# DaughterBoardInterface.net
KiCad netlist of a schematic drawn in Altium Designer
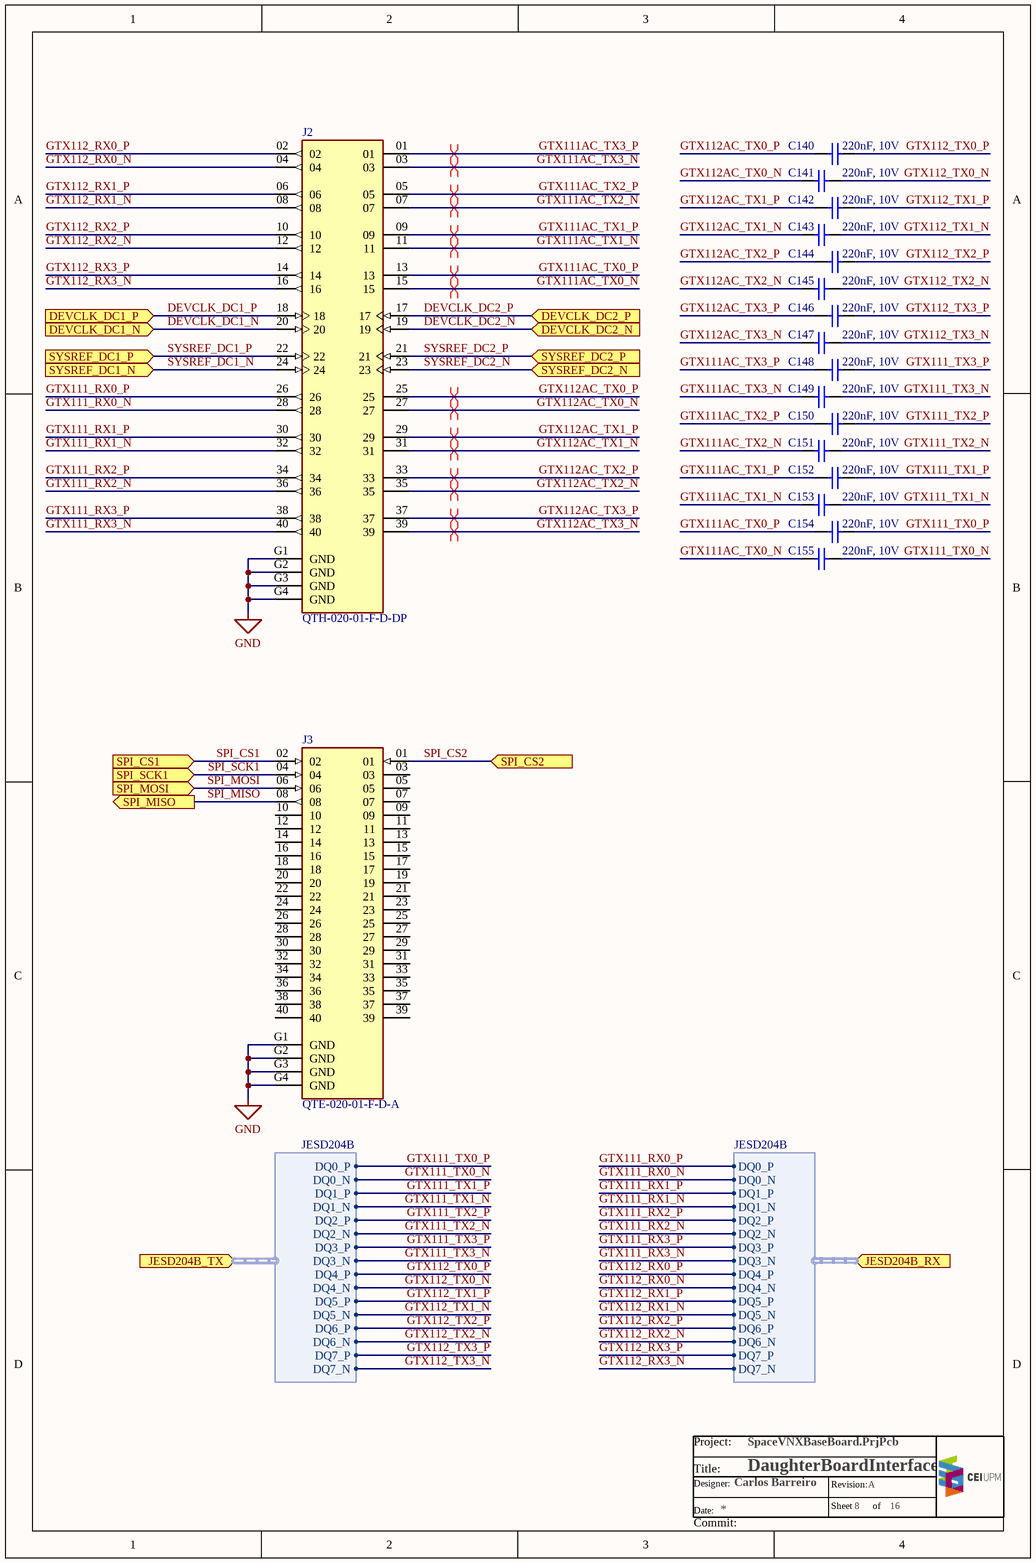
[diagram p0: DaughterBoardInterface.SchDoc]

(export (version "E")
  (design (tool "Eeschema 10.0.6"))
  (components
    (comp (ref "C140")
      (value "220nF, 10V")
      (footprint "WURTH_WCAP-CSGP_0402")
      (description "WCAP-CSGP Multilayer Ceramic Chip Capacitor, General Purpose, size 0402, X5R, 220nF, 10V")
      (fields
        (field (name "MANUFACTURER PART NUMBER") "885012105011")
        (field (name "MANUFACTURER") "Wurth Elektronik")
      )
      (libsource (lib "SpaceVNX") (part "885012105011"))
    )
    (comp (ref "C141")
      (value "220nF, 10V")
      (footprint "WURTH_WCAP-CSGP_0402")
      (description "WCAP-CSGP Multilayer Ceramic Chip Capacitor, General Purpose, size 0402, X5R, 220nF, 10V")
      (fields
        (field (name "MANUFACTURER PART NUMBER") "885012105011")
        (field (name "MANUFACTURER") "Wurth Elektronik")
      )
      (libsource (lib "SpaceVNX") (part "885012105011"))
    )
    (comp (ref "C142")
      (value "220nF, 10V")
      (footprint "WURTH_WCAP-CSGP_0402")
      (description "WCAP-CSGP Multilayer Ceramic Chip Capacitor, General Purpose, size 0402, X5R, 220nF, 10V")
      (fields
        (field (name "MANUFACTURER PART NUMBER") "885012105011")
        (field (name "MANUFACTURER") "Wurth Elektronik")
      )
      (libsource (lib "SpaceVNX") (part "885012105011"))
    )
    (comp (ref "C143")
      (value "220nF, 10V")
      (footprint "WURTH_WCAP-CSGP_0402")
      (description "WCAP-CSGP Multilayer Ceramic Chip Capacitor, General Purpose, size 0402, X5R, 220nF, 10V")
      (fields
        (field (name "MANUFACTURER PART NUMBER") "885012105011")
        (field (name "MANUFACTURER") "Wurth Elektronik")
      )
      (libsource (lib "SpaceVNX") (part "885012105011"))
    )
    (comp (ref "C144")
      (value "220nF, 10V")
      (footprint "WURTH_WCAP-CSGP_0402")
      (description "WCAP-CSGP Multilayer Ceramic Chip Capacitor, General Purpose, size 0402, X5R, 220nF, 10V")
      (fields
        (field (name "MANUFACTURER PART NUMBER") "885012105011")
        (field (name "MANUFACTURER") "Wurth Elektronik")
      )
      (libsource (lib "SpaceVNX") (part "885012105011"))
    )
    (comp (ref "C145")
      (value "220nF, 10V")
      (footprint "WURTH_WCAP-CSGP_0402")
      (description "WCAP-CSGP Multilayer Ceramic Chip Capacitor, General Purpose, size 0402, X5R, 220nF, 10V")
      (fields
        (field (name "MANUFACTURER PART NUMBER") "885012105011")
        (field (name "MANUFACTURER") "Wurth Elektronik")
      )
      (libsource (lib "SpaceVNX") (part "885012105011"))
    )
    (comp (ref "C146")
      (value "220nF, 10V")
      (footprint "WURTH_WCAP-CSGP_0402")
      (description "WCAP-CSGP Multilayer Ceramic Chip Capacitor, General Purpose, size 0402, X5R, 220nF, 10V")
      (fields
        (field (name "MANUFACTURER PART NUMBER") "885012105011")
        (field (name "MANUFACTURER") "Wurth Elektronik")
      )
      (libsource (lib "SpaceVNX") (part "885012105011"))
    )
    (comp (ref "C147")
      (value "220nF, 10V")
      (footprint "WURTH_WCAP-CSGP_0402")
      (description "WCAP-CSGP Multilayer Ceramic Chip Capacitor, General Purpose, size 0402, X5R, 220nF, 10V")
      (fields
        (field (name "MANUFACTURER PART NUMBER") "885012105011")
        (field (name "MANUFACTURER") "Wurth Elektronik")
      )
      (libsource (lib "SpaceVNX") (part "885012105011"))
    )
    (comp (ref "C148")
      (value "220nF, 10V")
      (footprint "WURTH_WCAP-CSGP_0402")
      (description "WCAP-CSGP Multilayer Ceramic Chip Capacitor, General Purpose, size 0402, X5R, 220nF, 10V")
      (fields
        (field (name "MANUFACTURER PART NUMBER") "885012105011")
        (field (name "MANUFACTURER") "Wurth Elektronik")
      )
      (libsource (lib "SpaceVNX") (part "885012105011"))
    )
    (comp (ref "C149")
      (value "220nF, 10V")
      (footprint "WURTH_WCAP-CSGP_0402")
      (description "WCAP-CSGP Multilayer Ceramic Chip Capacitor, General Purpose, size 0402, X5R, 220nF, 10V")
      (fields
        (field (name "MANUFACTURER PART NUMBER") "885012105011")
        (field (name "MANUFACTURER") "Wurth Elektronik")
      )
      (libsource (lib "SpaceVNX") (part "885012105011"))
    )
    (comp (ref "C150")
      (value "220nF, 10V")
      (footprint "WURTH_WCAP-CSGP_0402")
      (description "WCAP-CSGP Multilayer Ceramic Chip Capacitor, General Purpose, size 0402, X5R, 220nF, 10V")
      (fields
        (field (name "MANUFACTURER PART NUMBER") "885012105011")
        (field (name "MANUFACTURER") "Wurth Elektronik")
      )
      (libsource (lib "SpaceVNX") (part "885012105011"))
    )
    (comp (ref "C151")
      (value "220nF, 10V")
      (footprint "WURTH_WCAP-CSGP_0402")
      (description "WCAP-CSGP Multilayer Ceramic Chip Capacitor, General Purpose, size 0402, X5R, 220nF, 10V")
      (fields
        (field (name "MANUFACTURER PART NUMBER") "885012105011")
        (field (name "MANUFACTURER") "Wurth Elektronik")
      )
      (libsource (lib "SpaceVNX") (part "885012105011"))
    )
    (comp (ref "C152")
      (value "220nF, 10V")
      (footprint "WURTH_WCAP-CSGP_0402")
      (description "WCAP-CSGP Multilayer Ceramic Chip Capacitor, General Purpose, size 0402, X5R, 220nF, 10V")
      (fields
        (field (name "MANUFACTURER PART NUMBER") "885012105011")
        (field (name "MANUFACTURER") "Wurth Elektronik")
      )
      (libsource (lib "SpaceVNX") (part "885012105011"))
    )
    (comp (ref "C153")
      (value "220nF, 10V")
      (footprint "WURTH_WCAP-CSGP_0402")
      (description "WCAP-CSGP Multilayer Ceramic Chip Capacitor, General Purpose, size 0402, X5R, 220nF, 10V")
      (fields
        (field (name "MANUFACTURER PART NUMBER") "885012105011")
        (field (name "MANUFACTURER") "Wurth Elektronik")
      )
      (libsource (lib "SpaceVNX") (part "885012105011"))
    )
    (comp (ref "C154")
      (value "220nF, 10V")
      (footprint "WURTH_WCAP-CSGP_0402")
      (description "WCAP-CSGP Multilayer Ceramic Chip Capacitor, General Purpose, size 0402, X5R, 220nF, 10V")
      (fields
        (field (name "MANUFACTURER PART NUMBER") "885012105011")
        (field (name "MANUFACTURER") "Wurth Elektronik")
      )
      (libsource (lib "SpaceVNX") (part "885012105011"))
    )
    (comp (ref "C155")
      (value "220nF, 10V")
      (footprint "WURTH_WCAP-CSGP_0402")
      (description "WCAP-CSGP Multilayer Ceramic Chip Capacitor, General Purpose, size 0402, X5R, 220nF, 10V")
      (fields
        (field (name "MANUFACTURER PART NUMBER") "885012105011")
        (field (name "MANUFACTURER") "Wurth Elektronik")
      )
      (libsource (lib "SpaceVNX") (part "885012105011"))
    )
    (comp (ref "J2")
      (value "QTH-020-01-F-D-DP")
      (footprint "SAMTEC_QTH-020-01-X-D-DP-A")
      (description "0.50 mm Q Pairs® High-Speed Ground Plane Terminal Strip, Differential Pair")
      (fields (field (name "MF") "Samtec"))
      (libsource (lib "SpaceVNX") (part "QTH-020-01-F-D-DP"))
    )
    (comp (ref "J3")
      (value "QTE-020-01-F-D-A")
      (footprint "SAMTEC_QTE-020-01-X-D-A")
      (description "40 Position Connector Header, Outer Shroud Contacts Surface Mount Gold")
      (fields (field (name "MF") "Samtec"))
      (libsource (lib "SpaceVNX") (part "QTE-020-01-F-D-A"))
    )
  )
  (nets
    (net (code "2") (name "/DEVCLK_DC1_N") (class "Default")
      (node (ref "J2") (pin "20") (pinfunction "20_20") (pintype "input"))
    )
    (net (code "3") (name "/DEVCLK_DC1_P") (class "Default")
      (node (ref "J2") (pin "18") (pinfunction "18_18") (pintype "input"))
    )
    (net (code "4") (name "/DEVCLK_DC2_N") (class "Default")
      (node (ref "J2") (pin "19") (pinfunction "19_19") (pintype "input"))
    )
    (net (code "5") (name "/DEVCLK_DC2_P") (class "Default")
      (node (ref "J2") (pin "17") (pinfunction "17_17") (pintype "input"))
    )
    (net (code "6") (name "/GTX111AC_TX0_N") (class "Default")
      (node (ref "C155") (pin "1") (pinfunction "1_1") (pintype "passive"))
      (node (ref "J2") (pin "15") (pinfunction "15_15") (pintype "passive"))
    )
    (net (code "7") (name "/GTX111AC_TX0_P") (class "Default")
      (node (ref "C154") (pin "1") (pinfunction "1_1") (pintype "passive"))
      (node (ref "J2") (pin "13") (pinfunction "13_13") (pintype "passive"))
    )
    (net (code "8") (name "/GTX111AC_TX1_N") (class "Default")
      (node (ref "C153") (pin "1") (pinfunction "1_1") (pintype "passive"))
      (node (ref "J2") (pin "11") (pinfunction "11_11") (pintype "passive"))
    )
    (net (code "9") (name "/GTX111AC_TX1_P") (class "Default")
      (node (ref "C152") (pin "1") (pinfunction "1_1") (pintype "passive"))
      (node (ref "J2") (pin "09") (pinfunction "09_09") (pintype "passive"))
    )
    (net (code "10") (name "/GTX111AC_TX2_N") (class "Default")
      (node (ref "C151") (pin "1") (pinfunction "1_1") (pintype "passive"))
      (node (ref "J2") (pin "07") (pinfunction "07_07") (pintype "passive"))
    )
    (net (code "11") (name "/GTX111AC_TX2_P") (class "Default")
      (node (ref "C150") (pin "1") (pinfunction "1_1") (pintype "passive"))
      (node (ref "J2") (pin "05") (pinfunction "05_05") (pintype "passive"))
    )
    (net (code "12") (name "/GTX111AC_TX3_N") (class "Default")
      (node (ref "C149") (pin "1") (pinfunction "1_1") (pintype "passive"))
      (node (ref "J2") (pin "03") (pinfunction "03_03") (pintype "passive"))
    )
    (net (code "13") (name "/GTX111AC_TX3_P") (class "Default")
      (node (ref "C148") (pin "1") (pinfunction "1_1") (pintype "passive"))
      (node (ref "J2") (pin "01") (pinfunction "01_01") (pintype "passive"))
    )
    (net (code "14") (name "/GTX111_RX0_N") (class "Default")
      (node (ref "J2") (pin "28") (pinfunction "28_28") (pintype "output"))
    )
    (net (code "15") (name "/GTX111_RX0_P") (class "Default")
      (node (ref "J2") (pin "26") (pinfunction "26_26") (pintype "output"))
    )
    (net (code "16") (name "/GTX111_RX1_N") (class "Default")
      (node (ref "J2") (pin "32") (pinfunction "32_32") (pintype "output"))
    )
    (net (code "17") (name "/GTX111_RX1_P") (class "Default")
      (node (ref "J2") (pin "30") (pinfunction "30_30") (pintype "output"))
    )
    (net (code "18") (name "/GTX111_RX2_N") (class "Default")
      (node (ref "J2") (pin "36") (pinfunction "36_36") (pintype "output"))
    )
    (net (code "19") (name "/GTX111_RX2_P") (class "Default")
      (node (ref "J2") (pin "34") (pinfunction "34_34") (pintype "output"))
    )
    (net (code "20") (name "/GTX111_RX3_N") (class "Default")
      (node (ref "J2") (pin "40") (pinfunction "40_40") (pintype "output"))
    )
    (net (code "21") (name "/GTX111_RX3_P") (class "Default")
      (node (ref "J2") (pin "38") (pinfunction "38_38") (pintype "output"))
    )
    (net (code "22") (name "/GTX111_TX0_N") (class "Default")
      (node (ref "C155") (pin "2") (pinfunction "2_2") (pintype "passive"))
    )
    (net (code "23") (name "/GTX111_TX0_P") (class "Default")
      (node (ref "C154") (pin "2") (pinfunction "2_2") (pintype "passive"))
    )
    (net (code "24") (name "/GTX111_TX1_N") (class "Default")
      (node (ref "C153") (pin "2") (pinfunction "2_2") (pintype "passive"))
    )
    (net (code "25") (name "/GTX111_TX1_P") (class "Default")
      (node (ref "C152") (pin "2") (pinfunction "2_2") (pintype "passive"))
    )
    (net (code "26") (name "/GTX111_TX2_N") (class "Default")
      (node (ref "C151") (pin "2") (pinfunction "2_2") (pintype "passive"))
    )
    (net (code "27") (name "/GTX111_TX2_P") (class "Default")
      (node (ref "C150") (pin "2") (pinfunction "2_2") (pintype "passive"))
    )
    (net (code "28") (name "/GTX111_TX3_N") (class "Default")
      (node (ref "C149") (pin "2") (pinfunction "2_2") (pintype "passive"))
    )
    (net (code "29") (name "/GTX111_TX3_P") (class "Default")
      (node (ref "C148") (pin "2") (pinfunction "2_2") (pintype "passive"))
    )
    (net (code "30") (name "/GTX112AC_TX0_N") (class "Default")
      (node (ref "C141") (pin "1") (pinfunction "1_1") (pintype "passive"))
      (node (ref "J2") (pin "27") (pinfunction "27_27") (pintype "passive"))
    )
    (net (code "31") (name "/GTX112AC_TX0_P") (class "Default")
      (node (ref "C140") (pin "1") (pinfunction "1_1") (pintype "passive"))
      (node (ref "J2") (pin "25") (pinfunction "25_25") (pintype "passive"))
    )
    (net (code "32") (name "/GTX112AC_TX1_N") (class "Default")
      (node (ref "C143") (pin "1") (pinfunction "1_1") (pintype "passive"))
      (node (ref "J2") (pin "31") (pinfunction "31_31") (pintype "passive"))
    )
    (net (code "33") (name "/GTX112AC_TX1_P") (class "Default")
      (node (ref "C142") (pin "1") (pinfunction "1_1") (pintype "passive"))
      (node (ref "J2") (pin "29") (pinfunction "29_29") (pintype "passive"))
    )
    (net (code "34") (name "/GTX112AC_TX2_N") (class "Default")
      (node (ref "C145") (pin "1") (pinfunction "1_1") (pintype "passive"))
      (node (ref "J2") (pin "35") (pinfunction "35_35") (pintype "passive"))
    )
    (net (code "35") (name "/GTX112AC_TX2_P") (class "Default")
      (node (ref "C144") (pin "1") (pinfunction "1_1") (pintype "passive"))
      (node (ref "J2") (pin "33") (pinfunction "33_33") (pintype "passive"))
    )
    (net (code "36") (name "/GTX112AC_TX3_N") (class "Default")
      (node (ref "C147") (pin "1") (pinfunction "1_1") (pintype "passive"))
      (node (ref "J2") (pin "39") (pinfunction "39_39") (pintype "passive"))
    )
    (net (code "37") (name "/GTX112AC_TX3_P") (class "Default")
      (node (ref "C146") (pin "1") (pinfunction "1_1") (pintype "passive"))
      (node (ref "J2") (pin "37") (pinfunction "37_37") (pintype "passive"))
    )
    (net (code "38") (name "/GTX112_RX0_N") (class "Default")
      (node (ref "J2") (pin "04") (pinfunction "04_04") (pintype "output"))
    )
    (net (code "39") (name "/GTX112_RX0_P") (class "Default")
      (node (ref "J2") (pin "02") (pinfunction "02_02") (pintype "output"))
    )
    (net (code "40") (name "/GTX112_RX1_N") (class "Default")
      (node (ref "J2") (pin "08") (pinfunction "08_08") (pintype "output"))
    )
    (net (code "41") (name "/GTX112_RX1_P") (class "Default")
      (node (ref "J2") (pin "06") (pinfunction "06_06") (pintype "output"))
    )
    (net (code "42") (name "/GTX112_RX2_N") (class "Default")
      (node (ref "J2") (pin "12") (pinfunction "12_12") (pintype "output"))
    )
    (net (code "43") (name "/GTX112_RX2_P") (class "Default")
      (node (ref "J2") (pin "10") (pinfunction "10_10") (pintype "output"))
    )
    (net (code "44") (name "/GTX112_RX3_N") (class "Default")
      (node (ref "J2") (pin "16") (pinfunction "16_16") (pintype "output"))
    )
    (net (code "45") (name "/GTX112_RX3_P") (class "Default")
      (node (ref "J2") (pin "14") (pinfunction "14_14") (pintype "output"))
    )
    (net (code "46") (name "/GTX112_TX0_N") (class "Default")
      (node (ref "C141") (pin "2") (pinfunction "2_2") (pintype "passive"))
    )
    (net (code "47") (name "/GTX112_TX0_P") (class "Default")
      (node (ref "C140") (pin "2") (pinfunction "2_2") (pintype "passive"))
    )
    (net (code "48") (name "/GTX112_TX1_N") (class "Default")
      (node (ref "C143") (pin "2") (pinfunction "2_2") (pintype "passive"))
    )
    (net (code "49") (name "/GTX112_TX1_P") (class "Default")
      (node (ref "C142") (pin "2") (pinfunction "2_2") (pintype "passive"))
    )
    (net (code "50") (name "/GTX112_TX2_N") (class "Default")
      (node (ref "C145") (pin "2") (pinfunction "2_2") (pintype "passive"))
    )
    (net (code "51") (name "/GTX112_TX2_P") (class "Default")
      (node (ref "C144") (pin "2") (pinfunction "2_2") (pintype "passive"))
    )
    (net (code "52") (name "/GTX112_TX3_N") (class "Default")
      (node (ref "C147") (pin "2") (pinfunction "2_2") (pintype "passive"))
    )
    (net (code "53") (name "/GTX112_TX3_P") (class "Default")
      (node (ref "C146") (pin "2") (pinfunction "2_2") (pintype "passive"))
    )
    (net (code "54") (name "/SPI_CS1") (class "Default")
      (node (ref "J3") (pin "02") (pinfunction "02_02") (pintype "input"))
    )
    (net (code "55") (name "/SPI_CS2") (class "Default")
      (node (ref "J3") (pin "01") (pinfunction "01_01") (pintype "input"))
    )
    (net (code "56") (name "/SPI_MISO") (class "Default")
      (node (ref "J3") (pin "08") (pinfunction "08_08") (pintype "output"))
    )
    (net (code "57") (name "/SPI_MOSI") (class "Default")
      (node (ref "J3") (pin "06") (pinfunction "06_06") (pintype "input"))
    )
    (net (code "58") (name "/SPI_SCK1") (class "Default")
      (node (ref "J3") (pin "04") (pinfunction "04_04") (pintype "input"))
    )
    (net (code "59") (name "/SYSREF_DC1_N") (class "Default")
      (node (ref "J2") (pin "24") (pinfunction "24_24") (pintype "input"))
    )
    (net (code "60") (name "/SYSREF_DC1_P") (class "Default")
      (node (ref "J2") (pin "22") (pinfunction "22_22") (pintype "input"))
    )
    (net (code "61") (name "/SYSREF_DC2_N") (class "Default")
      (node (ref "J2") (pin "23") (pinfunction "23_23") (pintype "input"))
    )
    (net (code "62") (name "/SYSREF_DC2_P") (class "Default")
      (node (ref "J2") (pin "21") (pinfunction "21_21") (pintype "input"))
    )
    (net (code "64") (name "GND") (class "Default")
      (node (ref "J2") (pin "G1") (pinfunction "GND_G1") (pintype "power_in"))
      (node (ref "J2") (pin "G2") (pinfunction "GND_G2") (pintype "power_in"))
      (node (ref "J2") (pin "G3") (pinfunction "GND_G3") (pintype "power_in"))
      (node (ref "J2") (pin "G4") (pinfunction "GND_G4") (pintype "power_in"))
      (node (ref "J3") (pin "G1") (pinfunction "GND_G1") (pintype "power_in"))
      (node (ref "J3") (pin "G2") (pinfunction "GND_G2") (pintype "power_in"))
      (node (ref "J3") (pin "G3") (pinfunction "GND_G3") (pintype "power_in"))
      (node (ref "J3") (pin "G4") (pinfunction "GND_G4") (pintype "power_in"))
    )
    (net (code "65") (name "unconnected-(J3-Pad03)") (class "Default")
      (node (ref "J3") (pin "03") (pinfunction "03_03") (pintype "passive"))
    )
    (net (code "66") (name "unconnected-(J3-Pad05)") (class "Default")
      (node (ref "J3") (pin "05") (pinfunction "05_05") (pintype "passive"))
    )
    (net (code "67") (name "unconnected-(J3-Pad07)") (class "Default")
      (node (ref "J3") (pin "07") (pinfunction "07_07") (pintype "passive"))
    )
    (net (code "68") (name "unconnected-(J3-Pad09)") (class "Default")
      (node (ref "J3") (pin "09") (pinfunction "09_09") (pintype "passive"))
    )
    (net (code "69") (name "unconnected-(J3-Pad10)") (class "Default")
      (node (ref "J3") (pin "10") (pinfunction "10_10") (pintype "passive"))
    )
    (net (code "70") (name "unconnected-(J3-Pad11)") (class "Default")
      (node (ref "J3") (pin "11") (pinfunction "11_11") (pintype "passive"))
    )
    (net (code "71") (name "unconnected-(J3-Pad12)") (class "Default")
      (node (ref "J3") (pin "12") (pinfunction "12_12") (pintype "passive"))
    )
    (net (code "72") (name "unconnected-(J3-Pad13)") (class "Default")
      (node (ref "J3") (pin "13") (pinfunction "13_13") (pintype "passive"))
    )
    (net (code "73") (name "unconnected-(J3-Pad14)") (class "Default")
      (node (ref "J3") (pin "14") (pinfunction "14_14") (pintype "passive"))
    )
    (net (code "74") (name "unconnected-(J3-Pad15)") (class "Default")
      (node (ref "J3") (pin "15") (pinfunction "15_15") (pintype "passive"))
    )
    (net (code "75") (name "unconnected-(J3-Pad16)") (class "Default")
      (node (ref "J3") (pin "16") (pinfunction "16_16") (pintype "passive"))
    )
    (net (code "76") (name "unconnected-(J3-Pad17)") (class "Default")
      (node (ref "J3") (pin "17") (pinfunction "17_17") (pintype "passive"))
    )
    (net (code "77") (name "unconnected-(J3-Pad18)") (class "Default")
      (node (ref "J3") (pin "18") (pinfunction "18_18") (pintype "passive"))
    )
    (net (code "78") (name "unconnected-(J3-Pad19)") (class "Default")
      (node (ref "J3") (pin "19") (pinfunction "19_19") (pintype "passive"))
    )
    (net (code "79") (name "unconnected-(J3-Pad20)") (class "Default")
      (node (ref "J3") (pin "20") (pinfunction "20_20") (pintype "passive"))
    )
    (net (code "80") (name "unconnected-(J3-Pad21)") (class "Default")
      (node (ref "J3") (pin "21") (pinfunction "21_21") (pintype "passive"))
    )
    (net (code "81") (name "unconnected-(J3-Pad22)") (class "Default")
      (node (ref "J3") (pin "22") (pinfunction "22_22") (pintype "passive"))
    )
    (net (code "82") (name "unconnected-(J3-Pad23)") (class "Default")
      (node (ref "J3") (pin "23") (pinfunction "23_23") (pintype "passive"))
    )
    (net (code "83") (name "unconnected-(J3-Pad24)") (class "Default")
      (node (ref "J3") (pin "24") (pinfunction "24_24") (pintype "passive"))
    )
    (net (code "84") (name "unconnected-(J3-Pad25)") (class "Default")
      (node (ref "J3") (pin "25") (pinfunction "25_25") (pintype "passive"))
    )
    (net (code "85") (name "unconnected-(J3-Pad26)") (class "Default")
      (node (ref "J3") (pin "26") (pinfunction "26_26") (pintype "passive"))
    )
    (net (code "86") (name "unconnected-(J3-Pad27)") (class "Default")
      (node (ref "J3") (pin "27") (pinfunction "27_27") (pintype "passive"))
    )
    (net (code "87") (name "unconnected-(J3-Pad28)") (class "Default")
      (node (ref "J3") (pin "28") (pinfunction "28_28") (pintype "passive"))
    )
    (net (code "88") (name "unconnected-(J3-Pad29)") (class "Default")
      (node (ref "J3") (pin "29") (pinfunction "29_29") (pintype "passive"))
    )
    (net (code "89") (name "unconnected-(J3-Pad30)") (class "Default")
      (node (ref "J3") (pin "30") (pinfunction "30_30") (pintype "passive"))
    )
    (net (code "90") (name "unconnected-(J3-Pad31)") (class "Default")
      (node (ref "J3") (pin "31") (pinfunction "31_31") (pintype "passive"))
    )
    (net (code "91") (name "unconnected-(J3-Pad32)") (class "Default")
      (node (ref "J3") (pin "32") (pinfunction "32_32") (pintype "passive"))
    )
    (net (code "92") (name "unconnected-(J3-Pad33)") (class "Default")
      (node (ref "J3") (pin "33") (pinfunction "33_33") (pintype "passive"))
    )
    (net (code "93") (name "unconnected-(J3-Pad34)") (class "Default")
      (node (ref "J3") (pin "34") (pinfunction "34_34") (pintype "passive"))
    )
    (net (code "94") (name "unconnected-(J3-Pad35)") (class "Default")
      (node (ref "J3") (pin "35") (pinfunction "35_35") (pintype "passive"))
    )
    (net (code "95") (name "unconnected-(J3-Pad36)") (class "Default")
      (node (ref "J3") (pin "36") (pinfunction "36_36") (pintype "passive"))
    )
    (net (code "96") (name "unconnected-(J3-Pad37)") (class "Default")
      (node (ref "J3") (pin "37") (pinfunction "37_37") (pintype "passive"))
    )
    (net (code "97") (name "unconnected-(J3-Pad38)") (class "Default")
      (node (ref "J3") (pin "38") (pinfunction "38_38") (pintype "passive"))
    )
    (net (code "98") (name "unconnected-(J3-Pad39)") (class "Default")
      (node (ref "J3") (pin "39") (pinfunction "39_39") (pintype "passive"))
    )
    (net (code "99") (name "unconnected-(J3-Pad40)") (class "Default")
      (node (ref "J3") (pin "40") (pinfunction "40_40") (pintype "passive"))
    )
  )
)
